# MusicalChristmasTree.net
KiCad netlist of a schematic drawn in EAGLE
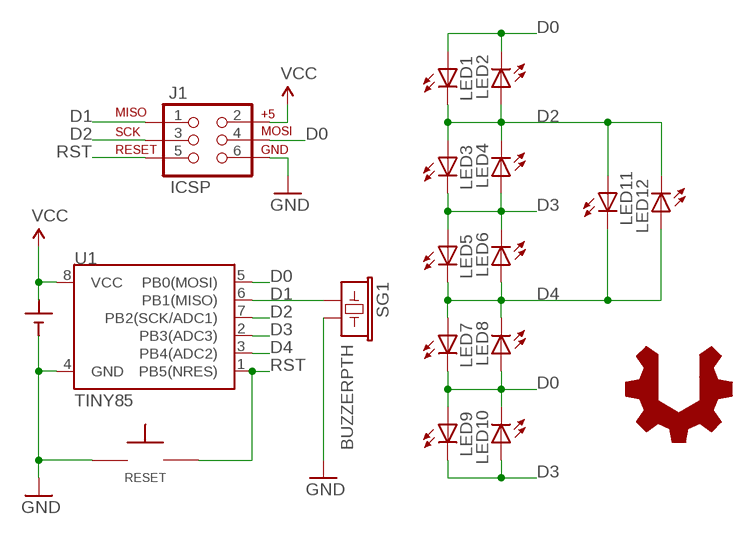
[diagram p0: schematic, sheet 1]

(export (version "E")
  (design (tool "Eeschema 10.0.6"))
  (components
    (comp (ref "BATT")
      (value "CR2032")
      (footprint "eagle-import:CR2032-THRU")
      (libsource (lib "eagle-import") (part "BATTCR2032_THRU"))
    )
    (comp (ref "J1")
      (value "ICSP")
      (footprint "eagle-import:2X3-NS")
      (libsource (lib "eagle-import") (part "AVR_SPI_PRG_6LABELED"))
    )
    (comp (ref "LED1")
      (value "LED5MM")
      (footprint "eagle-import:LED5MM")
      (libsource (lib "eagle-import") (part "LED5MM"))
    )
    (comp (ref "LED2")
      (value "LED5MM")
      (footprint "eagle-import:LED5MM")
      (libsource (lib "eagle-import") (part "LED5MM"))
    )
    (comp (ref "LED3")
      (value "LED5MM")
      (footprint "eagle-import:LED5MM")
      (libsource (lib "eagle-import") (part "LED5MM"))
    )
    (comp (ref "LED4")
      (value "LED5MM")
      (footprint "eagle-import:LED5MM")
      (libsource (lib "eagle-import") (part "LED5MM"))
    )
    (comp (ref "LED5")
      (value "LED5MM")
      (footprint "eagle-import:LED5MM")
      (libsource (lib "eagle-import") (part "LED5MM"))
    )
    (comp (ref "LED6")
      (value "LED5MM")
      (footprint "eagle-import:LED5MM")
      (libsource (lib "eagle-import") (part "LED5MM"))
    )
    (comp (ref "LED7")
      (value "LED5MM")
      (footprint "eagle-import:LED5MM")
      (libsource (lib "eagle-import") (part "LED5MM"))
    )
    (comp (ref "LED8")
      (value "LED5MM")
      (footprint "eagle-import:LED5MM")
      (libsource (lib "eagle-import") (part "LED5MM"))
    )
    (comp (ref "LED9")
      (value "LED5MM")
      (footprint "eagle-import:LED5MM")
      (libsource (lib "eagle-import") (part "LED5MM"))
    )
    (comp (ref "LED10")
      (value "LED5MM")
      (footprint "eagle-import:LED5MM")
      (libsource (lib "eagle-import") (part "LED5MM"))
    )
    (comp (ref "LED11")
      (value "LED5MM")
      (footprint "eagle-import:LED5MM")
      (libsource (lib "eagle-import") (part "LED5MM"))
    )
    (comp (ref "LED12")
      (value "LED5MM")
      (footprint "eagle-import:LED5MM")
      (libsource (lib "eagle-import") (part "LED5MM"))
    )
    (comp (ref "RESET")
      (value "TAC_SPST_NO")
      (footprint "eagle-import:TAC_SPST_NO")
      (libsource (lib "eagle-import") (part "TAC_SPST_NO"))
    )
    (comp (ref "SG1")
      (value "BUZZERPTH")
      (footprint "eagle-import:BUZZER-12MM")
      (libsource (lib "eagle-import") (part "BUZZERPTH"))
    )
    (comp (ref "U$1")
      (value "USER_HACKABLE")
      (footprint "eagle-import:USER_HACKABLE")
      (libsource (lib "eagle-import") (part "USER_HACKABLE"))
    )
    (comp (ref "U1")
      (value "TINY85")
      (footprint "eagle-import:DIP08")
      (libsource (lib "eagle-import") (part "ATTINY45TINY85-20-DIP"))
    )
  )
  (nets
    (net (code "1") (name "/D0") (class "Default")
      (node (ref "J1") (pin "4") (pinfunction "MOSI_4") (pintype "passive"))
      (node (ref "LED1") (pin "A") (pinfunction "A_A") (pintype "passive"))
      (node (ref "LED10") (pin "K") (pinfunction "C_K") (pintype "passive"))
      (node (ref "LED2") (pin "K") (pinfunction "C_K") (pintype "passive"))
      (node (ref "LED7") (pin "K") (pinfunction "C_K") (pintype "passive"))
      (node (ref "LED8") (pin "A") (pinfunction "A_A") (pintype "passive"))
      (node (ref "LED9") (pin "A") (pinfunction "A_A") (pintype "passive"))
      (node (ref "U1") (pin "5") (pinfunction "PB0(MOSI)_5") (pintype "bidirectional"))
    )
    (net (code "2") (name "/D1") (class "Default")
      (node (ref "J1") (pin "1") (pinfunction "MISO_1") (pintype "passive"))
      (node (ref "SG1") (pin "+") (pinfunction "1_+") (pintype "passive"))
      (node (ref "U1") (pin "6") (pinfunction "PB1(MISO)_6") (pintype "bidirectional"))
    )
    (net (code "3") (name "/D2") (class "Default")
      (node (ref "J1") (pin "3") (pinfunction "SCK_3") (pintype "passive"))
      (node (ref "LED1") (pin "K") (pinfunction "C_K") (pintype "passive"))
      (node (ref "LED11") (pin "A") (pinfunction "A_A") (pintype "passive"))
      (node (ref "LED12") (pin "K") (pinfunction "C_K") (pintype "passive"))
      (node (ref "LED2") (pin "A") (pinfunction "A_A") (pintype "passive"))
      (node (ref "LED3") (pin "A") (pinfunction "A_A") (pintype "passive"))
      (node (ref "LED4") (pin "K") (pinfunction "C_K") (pintype "passive"))
      (node (ref "U1") (pin "7") (pinfunction "PB2(SCK/ADC1)_7") (pintype "bidirectional"))
    )
    (net (code "4") (name "/D3") (class "Default")
      (node (ref "LED10") (pin "A") (pinfunction "A_A") (pintype "passive"))
      (node (ref "LED3") (pin "K") (pinfunction "C_K") (pintype "passive"))
      (node (ref "LED4") (pin "A") (pinfunction "A_A") (pintype "passive"))
      (node (ref "LED5") (pin "A") (pinfunction "A_A") (pintype "passive"))
      (node (ref "LED6") (pin "K") (pinfunction "C_K") (pintype "passive"))
      (node (ref "LED9") (pin "K") (pinfunction "C_K") (pintype "passive"))
      (node (ref "U1") (pin "2") (pinfunction "PB3(ADC3)_2") (pintype "bidirectional"))
    )
    (net (code "5") (name "/D4") (class "Default")
      (node (ref "LED11") (pin "K") (pinfunction "C_K") (pintype "passive"))
      (node (ref "LED12") (pin "A") (pinfunction "A_A") (pintype "passive"))
      (node (ref "LED5") (pin "K") (pinfunction "C_K") (pintype "passive"))
      (node (ref "LED6") (pin "A") (pinfunction "A_A") (pintype "passive"))
      (node (ref "LED7") (pin "A") (pinfunction "A_A") (pintype "passive"))
      (node (ref "LED8") (pin "K") (pinfunction "C_K") (pintype "passive"))
      (node (ref "U1") (pin "3") (pinfunction "PB4(ADC2)_3") (pintype "bidirectional"))
    )
    (net (code "6") (name "/RST") (class "Default")
      (node (ref "J1") (pin "5") (pinfunction "RST_5") (pintype "passive"))
      (node (ref "RESET") (pin "P$2") (pinfunction "P$2_P$2") (pintype "bidirectional"))
      (node (ref "U1") (pin "1") (pinfunction "PB5(NRES)_1") (pintype "bidirectional"))
    )
    (net (code "7") (name "GND") (class "Default")
      (node (ref "BATT") (pin "-") (pinfunction "-_-") (pintype "power_in"))
      (node (ref "J1") (pin "6") (pinfunction "GND_6") (pintype "passive"))
      (node (ref "RESET") (pin "P$1") (pinfunction "P$1_P$1") (pintype "bidirectional"))
      (node (ref "SG1") (pin "-") (pinfunction "2_-") (pintype "passive"))
      (node (ref "U1") (pin "4") (pinfunction "GND_4") (pintype "bidirectional"))
    )
    (net (code "8") (name "VCC") (class "Default")
      (node (ref "BATT") (pin "+1") (pinfunction "+_+1") (pintype "power_in"))
      (node (ref "J1") (pin "2") (pinfunction "V+_2") (pintype "passive"))
      (node (ref "U1") (pin "8") (pinfunction "VCC_8") (pintype "bidirectional"))
    )
  )
)
